# ui_audio.net
KiCad netlist of a schematic drawn in Altium Designer
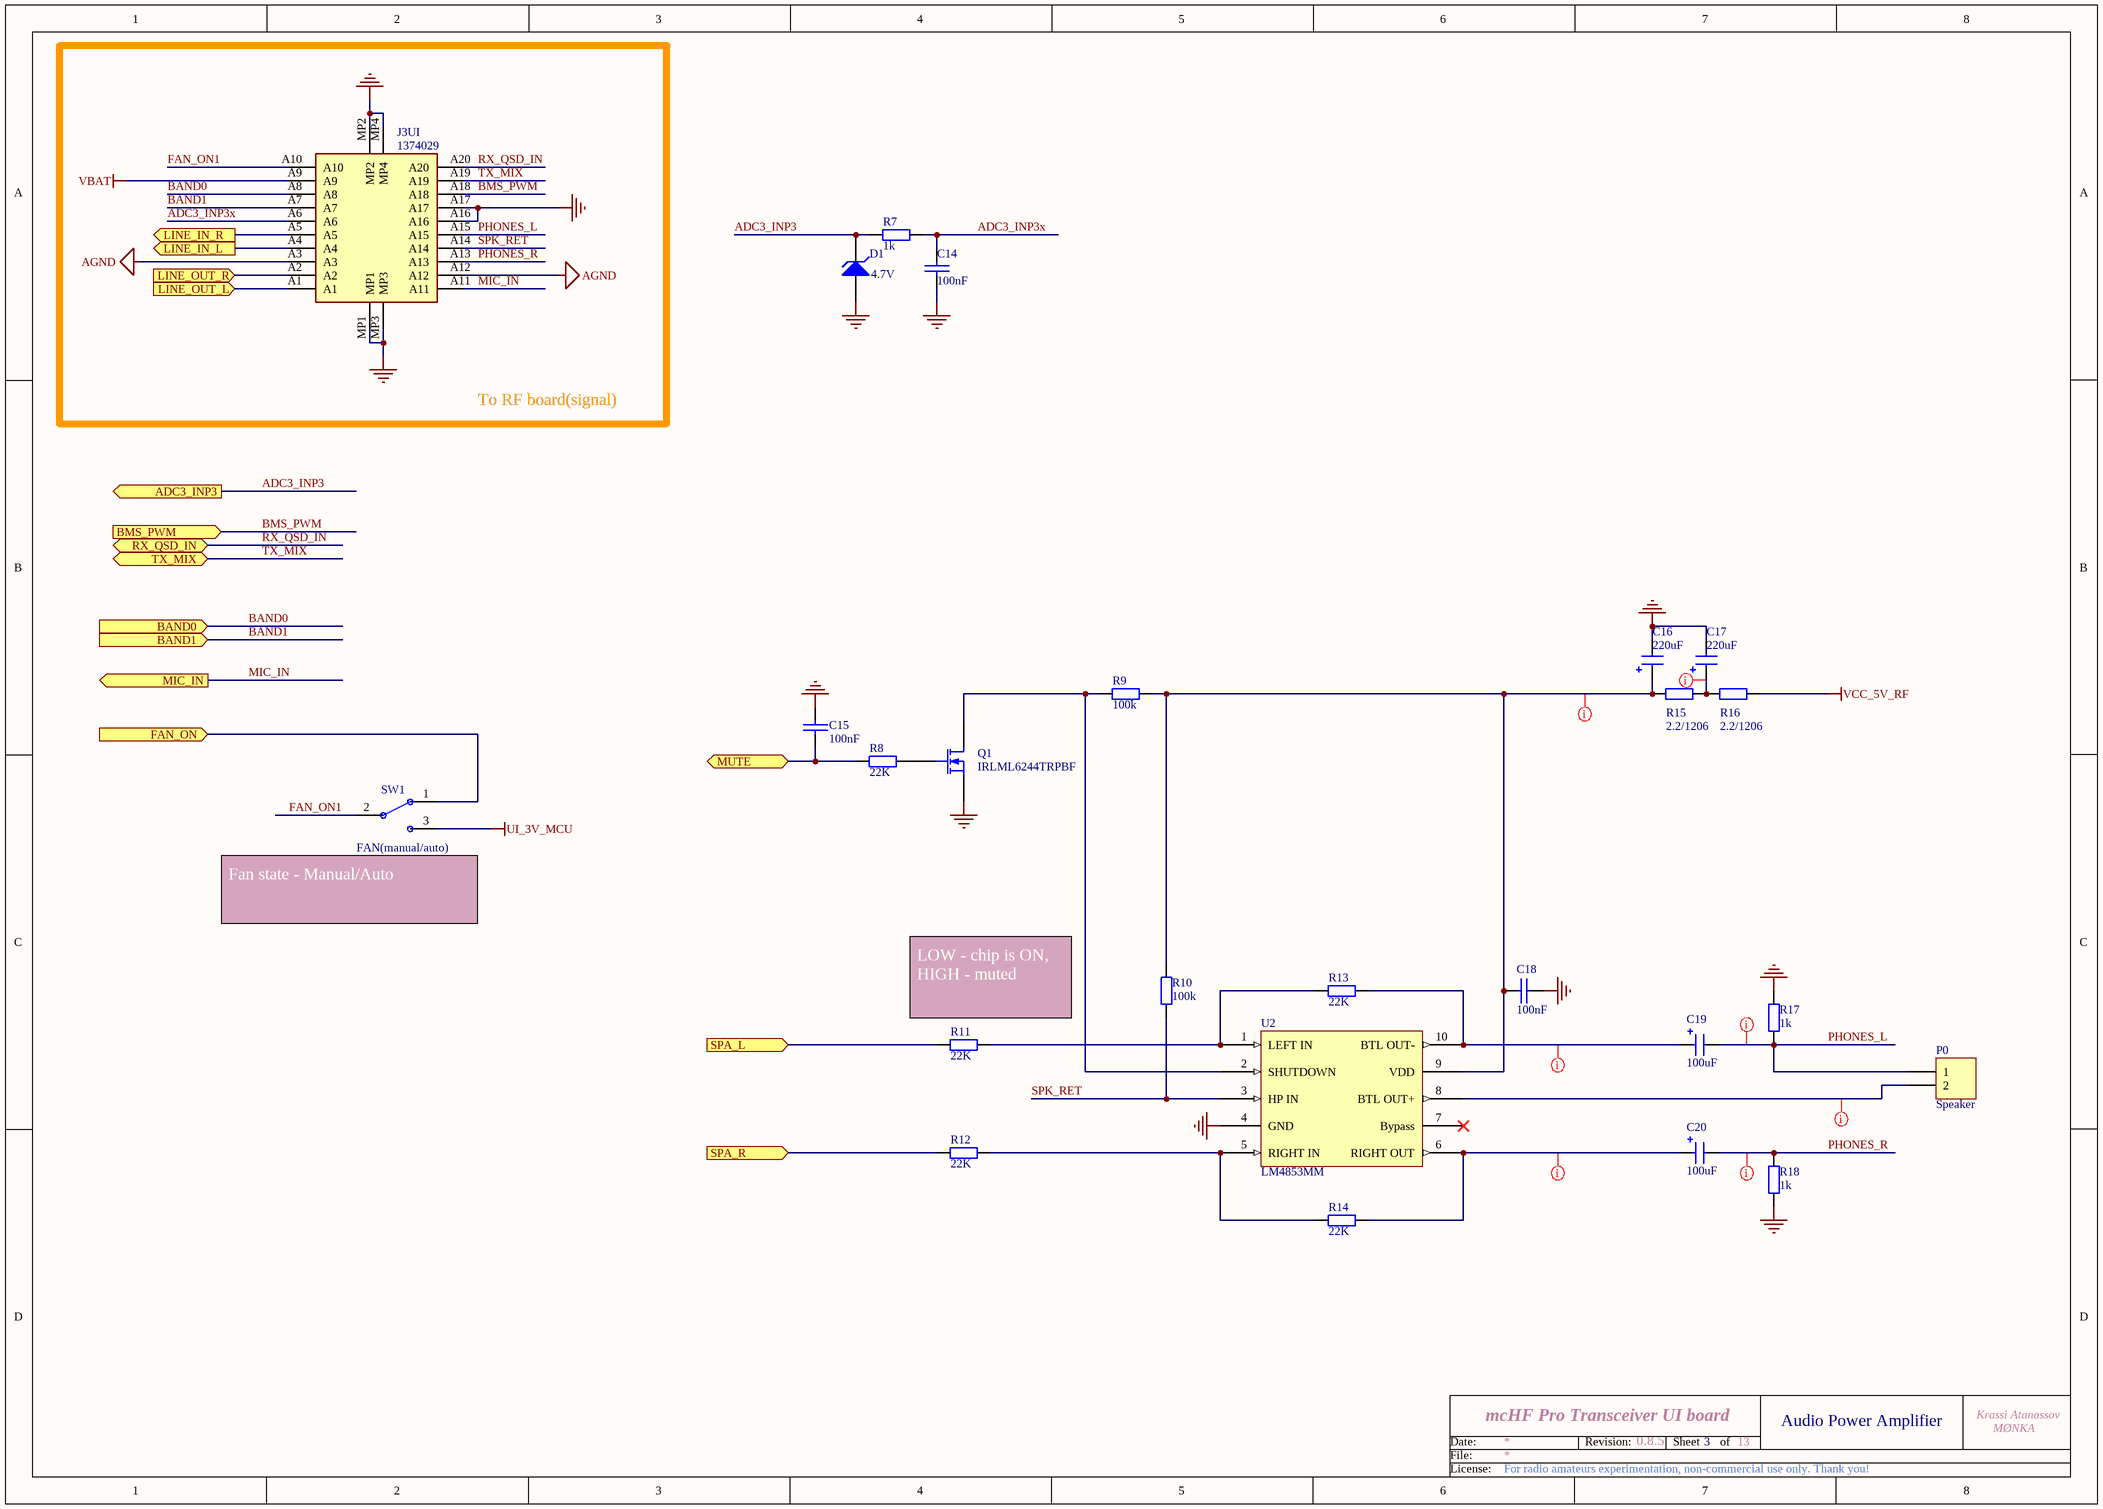
[diagram p0: ui_audio.SchDoc]

(export (version "E")
  (design (tool "Eeschema 10.0.6"))
  (components
    (comp (ref "C14")
      (value "100nF")
      (footprint "0805")
      (description "Capacitor")
      (libsource (lib "mcHF_ui") (part "CAP"))
    )
    (comp (ref "C15")
      (value "100nF")
      (footprint "0805")
      (description "Capacitor")
      (libsource (lib "mcHF_ui") (part "CAP"))
    )
    (comp (ref "C16")
      (value "220uF")
      (footprint "CAP_ALUM_Pro")
      (description "Electrolitic capacitor")
      (libsource (lib "mcHF_ui") (part "CAP-POL"))
    )
    (comp (ref "C17")
      (value "220uF")
      (footprint "CAP_ALUM_Pro")
      (description "Electrolitic capacitor")
      (libsource (lib "mcHF_ui") (part "CAP-POL"))
    )
    (comp (ref "C18")
      (value "100nF")
      (footprint "0805")
      (description "Capacitor")
      (libsource (lib "mcHF_ui") (part "CAP"))
    )
    (comp (ref "C19")
      (value "100uF")
      (footprint "CAP_ALUM_Pro")
      (description "Electrolitic capacitor")
      (libsource (lib "mcHF_ui") (part "CAP-POL"))
    )
    (comp (ref "C20")
      (value "100uF")
      (footprint "CAP_ALUM_Pro")
      (description "Electrolitic capacitor")
      (libsource (lib "mcHF_ui") (part "CAP-POL"))
    )
    (comp (ref "D1")
      (value "4.7V")
      (footprint "0805P")
      (description "Zener Diode")
      (fields (field (name "PUBLISHER") "Altium Limited"))
      (libsource (lib "Miscellaneous Devices") (part "D Zener"))
    )
    (comp (ref "J3UI")
      (value "1374029")
      (footprint "1373866")
      (fields
        (field (name "MOUSER PART NUMBER") "651-1373866")
        (field (name "MANUFACTURER_PART_NUMBER") "1373866")
      )
      (libsource (lib "1373866") (part "1373866"))
    )
    (comp (ref "P0")
      (value "Speaker")
      (footprint "MHDR1X2_m")
      (description "Header, 2-Pin")
      (fields (field (name "PUBLISHER") "Altium Limited"))
      (libsource (lib "Miscellaneous Connectors") (part "MHDR1X2"))
    )
    (comp (ref "Q1")
      (value "IRLML6244TRPBF")
      (footprint "SOT-23")
      (description "N-Channel MOSFET")
      (libsource (lib "mcHF_ui_b") (part "MOSFET-N"))
    )
    (comp (ref "R7")
      (value "1k")
      (footprint "0805")
      (description "Resistor")
      (libsource (lib "") (part "RES_1"))
    )
    (comp (ref "R8")
      (value "22K")
      (footprint "0805")
      (description "Resistor")
      (libsource (lib "") (part "RES_1"))
    )
    (comp (ref "R9")
      (value "100k")
      (footprint "0805")
      (description "Resistor")
      (libsource (lib "") (part "RES_1"))
    )
    (comp (ref "R10")
      (value "100k")
      (footprint "0805")
      (description "Resistor")
      (libsource (lib "") (part "RES_2"))
    )
    (comp (ref "R11")
      (value "22K")
      (footprint "0805")
      (description "Resistor")
      (libsource (lib "") (part "RES_1"))
    )
    (comp (ref "R12")
      (value "22K")
      (footprint "0805")
      (description "Resistor")
      (libsource (lib "") (part "RES_1"))
    )
    (comp (ref "R13")
      (value "22K")
      (footprint "0805")
      (description "Resistor")
      (libsource (lib "") (part "RES_1"))
    )
    (comp (ref "R14")
      (value "22K")
      (footprint "0805")
      (description "Resistor")
      (libsource (lib "") (part "RES_1"))
    )
    (comp (ref "R15")
      (value "2.2/1206")
      (footprint "1206")
      (description "Resistor")
      (libsource (lib "") (part "RES_1"))
    )
    (comp (ref "R16")
      (value "2.2/1206")
      (footprint "1206")
      (description "Resistor")
      (libsource (lib "") (part "RES_1"))
    )
    (comp (ref "R17")
      (value "1k")
      (footprint "0805")
      (description "Resistor")
      (libsource (lib "mcHF_ui") (part "RES"))
    )
    (comp (ref "R18")
      (value "1k")
      (footprint "0805")
      (description "Resistor")
      (libsource (lib "mcHF_ui") (part "RES"))
    )
    (comp (ref "SW1")
      (value "FAN(manual/auto)")
      (footprint "SW3")
      (description "Three pole switch")
      (libsource (lib "__ui") (part "SW3"))
    )
    (comp (ref "U2")
      (value "LM4853MM")
      (footprint "__ui:SLAB-MSOP-10_N")
      (description "Mono 1.5 W / Stereo 300mW Power Amplifier")
      (libsource (lib "__ui") (part "LM4853"))
    )
  )
  (nets
    (net (code "1") (name "/ADC3_INP3") (class "Default")
      (node (ref "D1") (pin "2") (pinfunction "K_2") (pintype "passive"))
      (node (ref "R7") (pin "2") (pinfunction "2_2") (pintype "passive"))
    )
    (net (code "2") (name "/ADC3_INP3x") (class "Default")
      (node (ref "C14") (pin "2") (pinfunction "2_2") (pintype "passive"))
      (node (ref "J3UI") (pin "A6") (pinfunction "A6_A6") (pintype "passive"))
      (node (ref "R7") (pin "1") (pinfunction "1_1") (pintype "passive"))
    )
    (net (code "3") (name "/BAND0") (class "Default")
      (node (ref "J3UI") (pin "A8") (pinfunction "A8_A8") (pintype "passive"))
    )
    (net (code "4") (name "/BAND1") (class "Default")
      (node (ref "J3UI") (pin "A7") (pinfunction "A7_A7") (pintype "passive"))
    )
    (net (code "5") (name "/BMS_PWM") (class "Default")
      (node (ref "J3UI") (pin "A18") (pinfunction "A18_A18") (pintype "passive"))
    )
    (net (code "6") (name "/FAN_ON") (class "Default")
      (node (ref "SW1") (pin "1") (pinfunction "1_1") (pintype "passive"))
    )
    (net (code "7") (name "/FAN_ON1") (class "Default")
      (node (ref "J3UI") (pin "A10") (pinfunction "A10_A10") (pintype "passive"))
      (node (ref "SW1") (pin "2") (pinfunction "2_2") (pintype "passive"))
    )
    (net (code "8") (name "/LINE_IN_L") (class "Default")
      (node (ref "J3UI") (pin "A4") (pinfunction "A4_A4") (pintype "passive"))
    )
    (net (code "9") (name "/LINE_IN_R") (class "Default")
      (node (ref "J3UI") (pin "A5") (pinfunction "A5_A5") (pintype "passive"))
    )
    (net (code "10") (name "/LINE_OUT_L") (class "Default")
      (node (ref "J3UI") (pin "A1") (pinfunction "A1_A1") (pintype "passive"))
    )
    (net (code "11") (name "/LINE_OUT_R") (class "Default")
      (node (ref "J3UI") (pin "A2") (pinfunction "A2_A2") (pintype "passive"))
    )
    (net (code "12") (name "/MIC_IN") (class "Default")
      (node (ref "J3UI") (pin "A11") (pinfunction "A11_A11") (pintype "passive"))
    )
    (net (code "13") (name "/MUTE") (class "Default")
      (node (ref "C15") (pin "2") (pinfunction "2_2") (pintype "passive"))
      (node (ref "R8") (pin "2") (pinfunction "2_2") (pintype "passive"))
    )
    (net (code "14") (name "/PHONES_L") (class "Default")
      (node (ref "C19") (pin "2") (pinfunction "2_2") (pintype "passive"))
      (node (ref "J3UI") (pin "A15") (pinfunction "A15_A15") (pintype "passive"))
      (node (ref "P0") (pin "1") (pinfunction "1_1") (pintype "passive"))
      (node (ref "R17") (pin "1") (pinfunction "1_1") (pintype "passive"))
    )
    (net (code "15") (name "/PHONES_R") (class "Default")
      (node (ref "C20") (pin "2") (pinfunction "2_2") (pintype "passive"))
      (node (ref "J3UI") (pin "A13") (pinfunction "A13_A13") (pintype "passive"))
      (node (ref "R18") (pin "2") (pinfunction "2_2") (pintype "passive"))
    )
    (net (code "16") (name "/RX_QSD_IN") (class "Default")
      (node (ref "J3UI") (pin "A20") (pinfunction "A20_A20") (pintype "passive"))
    )
    (net (code "17") (name "/SPA_L") (class "Default")
      (node (ref "R11") (pin "2") (pinfunction "2_2") (pintype "passive"))
    )
    (net (code "18") (name "/SPA_R") (class "Default")
      (node (ref "R12") (pin "2") (pinfunction "2_2") (pintype "passive"))
    )
    (net (code "19") (name "/SPK_RET") (class "Default")
      (node (ref "J3UI") (pin "A14") (pinfunction "A14_A14") (pintype "passive"))
      (node (ref "R10") (pin "2") (pinfunction "2_2") (pintype "passive"))
      (node (ref "U2") (pin "3") (pinfunction "HP_IN_3") (pintype "input"))
    )
    (net (code "20") (name "/TX_MIX") (class "Default")
      (node (ref "J3UI") (pin "A19") (pinfunction "A19_A19") (pintype "passive"))
    )
    (net (code "21") (name "AGND") (class "Default")
      (node (ref "J3UI") (pin "A12") (pinfunction "A12_A12") (pintype "passive"))
      (node (ref "J3UI") (pin "A3") (pinfunction "A3_A3") (pintype "passive"))
    )
    (net (code "22") (name "GND") (class "Default")
      (node (ref "C14") (pin "1") (pinfunction "1_1") (pintype "passive"))
      (node (ref "C15") (pin "1") (pinfunction "1_1") (pintype "passive"))
      (node (ref "C16") (pin "2") (pinfunction "2_2") (pintype "passive"))
      (node (ref "C17") (pin "2") (pinfunction "2_2") (pintype "passive"))
      (node (ref "C18") (pin "1") (pinfunction "1_1") (pintype "passive"))
      (node (ref "D1") (pin "1") (pinfunction "A_1") (pintype "passive"))
      (node (ref "J3UI") (pin "A16") (pinfunction "A16_A16") (pintype "passive"))
      (node (ref "J3UI") (pin "A17") (pinfunction "A17_A17") (pintype "passive"))
      (node (ref "J3UI") (pin "MP1") (pinfunction "MP1_MP1") (pintype "passive"))
      (node (ref "J3UI") (pin "MP2") (pinfunction "MP2_MP2") (pintype "passive"))
      (node (ref "J3UI") (pin "MP3") (pinfunction "MP3_MP3") (pintype "passive"))
      (node (ref "J3UI") (pin "MP4") (pinfunction "MP4_MP4") (pintype "passive"))
      (node (ref "Q1") (pin "2") (pinfunction "S_2") (pintype "passive"))
      (node (ref "R17") (pin "2") (pinfunction "2_2") (pintype "passive"))
      (node (ref "R18") (pin "1") (pinfunction "1_1") (pintype "passive"))
      (node (ref "U2") (pin "4") (pinfunction "GND_4") (pintype "power_in"))
    )
    (net (code "23") (name "Net-(C17-Pad1)") (class "Default")
      (node (ref "C17") (pin "1") (pinfunction "1_1") (pintype "passive"))
      (node (ref "R15") (pin "1") (pinfunction "1_1") (pintype "passive"))
      (node (ref "R16") (pin "2") (pinfunction "2_2") (pintype "passive"))
    )
    (net (code "24") (name "Net-(Q1-D)") (class "Default")
      (node (ref "Q1") (pin "3") (pinfunction "D_3") (pintype "passive"))
      (node (ref "R9") (pin "2") (pinfunction "2_2") (pintype "passive"))
      (node (ref "U2") (pin "2") (pinfunction "SHUTDOWN_2") (pintype "input"))
    )
    (net (code "25") (name "Net-(Q1-G)") (class "Default")
      (node (ref "Q1") (pin "1") (pinfunction "G_1") (pintype "passive"))
      (node (ref "R8") (pin "1") (pinfunction "1_1") (pintype "passive"))
    )
    (net (code "26") (name "Net-(U2-BTL_OUT+)") (class "Default")
      (node (ref "P0") (pin "2") (pinfunction "2_2") (pintype "passive"))
      (node (ref "U2") (pin "8") (pinfunction "BTL_OUT+_8") (pintype "output"))
    )
    (net (code "27") (name "Net-(U2-BTL_OUT-)") (class "Default")
      (node (ref "C19") (pin "1") (pinfunction "1_1") (pintype "passive"))
      (node (ref "R13") (pin "1") (pinfunction "1_1") (pintype "passive"))
      (node (ref "U2") (pin "10") (pinfunction "BTL_OUT-_10") (pintype "output"))
    )
    (net (code "28") (name "Net-(U2-LEFT_IN)") (class "Default")
      (node (ref "R11") (pin "1") (pinfunction "1_1") (pintype "passive"))
      (node (ref "R13") (pin "2") (pinfunction "2_2") (pintype "passive"))
      (node (ref "U2") (pin "1") (pinfunction "LEFT_IN_1") (pintype "input"))
    )
    (net (code "29") (name "Net-(U2-RIGHT_IN)") (class "Default")
      (node (ref "R12") (pin "1") (pinfunction "1_1") (pintype "passive"))
      (node (ref "R14") (pin "2") (pinfunction "2_2") (pintype "passive"))
      (node (ref "U2") (pin "5") (pinfunction "RIGHT_IN_5") (pintype "input"))
    )
    (net (code "30") (name "Net-(U2-RIGHT_OUT)") (class "Default")
      (node (ref "C20") (pin "1") (pinfunction "1_1") (pintype "passive"))
      (node (ref "R14") (pin "1") (pinfunction "1_1") (pintype "passive"))
      (node (ref "U2") (pin "6") (pinfunction "RIGHT_OUT_6") (pintype "output"))
    )
    (net (code "31") (name "Net-(U2-VDD)") (class "Default")
      (node (ref "C16") (pin "1") (pinfunction "1_1") (pintype "passive"))
      (node (ref "C18") (pin "2") (pinfunction "2_2") (pintype "passive"))
      (node (ref "R10") (pin "1") (pinfunction "1_1") (pintype "passive"))
      (node (ref "R15") (pin "2") (pinfunction "2_2") (pintype "passive"))
      (node (ref "R9") (pin "1") (pinfunction "1_1") (pintype "passive"))
      (node (ref "U2") (pin "9") (pinfunction "VDD_9") (pintype "passive"))
    )
    (net (code "32") (name "UI_3V_MCU") (class "Default")
      (node (ref "SW1") (pin "3") (pinfunction "3_3") (pintype "passive"))
    )
    (net (code "33") (name "VBAT") (class "Default")
      (node (ref "J3UI") (pin "A9") (pinfunction "A9_A9") (pintype "passive"))
    )
    (net (code "34") (name "VCC_5V_RF") (class "Default")
      (node (ref "R16") (pin "1") (pinfunction "1_1") (pintype "passive"))
    )
    (net (code "35") (name "unconnected-(U2-Bypass-Pad7)") (class "Default")
      (node (ref "U2") (pin "7") (pinfunction "Bypass_7") (pintype "passive+no_connect"))
    )
  )
)
